# throughhole.net
KiCad netlist of a schematic drawn in EAGLE
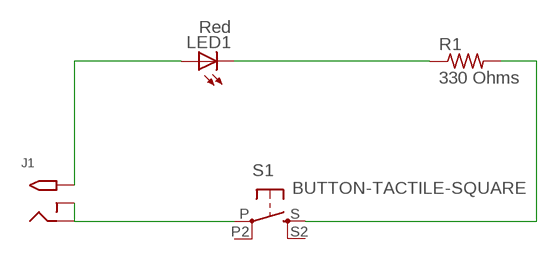
[diagram p0: schematic, sheet 1]

(export (version "E")
  (design (tool "Eeschema 10.0.6"))
  (components
    (comp (ref "J1")
      (value "2.1MMJACKTHM")
      (footprint "eagle-import:PJ-102A")
      (libsource (lib "eagle-import") (part "2.1MMJACKTHM"))
    )
    (comp (ref "LED1")
      (value "Red")
      (footprint "eagle-import:LED5MM")
      (libsource (lib "eagle-import") (part "LED5MM"))
    )
    (comp (ref "R1")
      (value "330 Ohms")
      (footprint "eagle-import:RESAD1160W55L680D260_HS")
      (libsource (lib "eagle-import") (part "RESISTORTH-1/4W-CARBON"))
    )
    (comp (ref "S1")
      (value "BUTTON-TACTILE-SQUARE")
      (footprint "eagle-import:BUTTON-TACTILE-SQUARE-ADAFRUIT1010")
      (libsource (lib "eagle-import") (part "BUTTON-TACTILE-SQUARE"))
    )
  )
  (nets
    (net (code "1") (name "Net-(J1-PadRING)") (class "Default")
      (node (ref "J1") (pin "RING") (pinfunction "RING_RING") (pintype "bidirectional"))
      (node (ref "J1") (pin "RING_SW") (pinfunction "RING_SW_RING_SW") (pintype "bidirectional"))
      (node (ref "S1") (pin "P") (pinfunction "P_P") (pintype "passive"))
    )
    (net (code "2") (name "Net-(J1-PadTIP)") (class "Default")
      (node (ref "J1") (pin "TIP") (pinfunction "TIP_TIP") (pintype "bidirectional"))
      (node (ref "LED1") (pin "A") (pinfunction "A_A") (pintype "passive"))
    )
    (net (code "3") (name "Net-(LED1-C)") (class "Default")
      (node (ref "LED1") (pin "K") (pinfunction "C_K") (pintype "passive"))
      (node (ref "R1") (pin "1") (pinfunction "1_1") (pintype "passive"))
    )
    (net (code "4") (name "Net-(R1-Pad2)") (class "Default")
      (node (ref "R1") (pin "2") (pinfunction "2_2") (pintype "passive"))
      (node (ref "S1") (pin "S") (pinfunction "S_S") (pintype "passive"))
    )
    (net (code "5") (name "unconnected-(S1-P1-PadP2)") (class "Default")
      (node (ref "S1") (pin "P2") (pinfunction "P1_P2") (pintype "passive"))
    )
    (net (code "6") (name "unconnected-(S1-S1-PadS2)") (class "Default")
      (node (ref "S1") (pin "S2") (pinfunction "S1_S2") (pintype "passive"))
    )
  )
)
